# TopSheet.net
KiCad netlist of a schematic drawn in Altium Designer
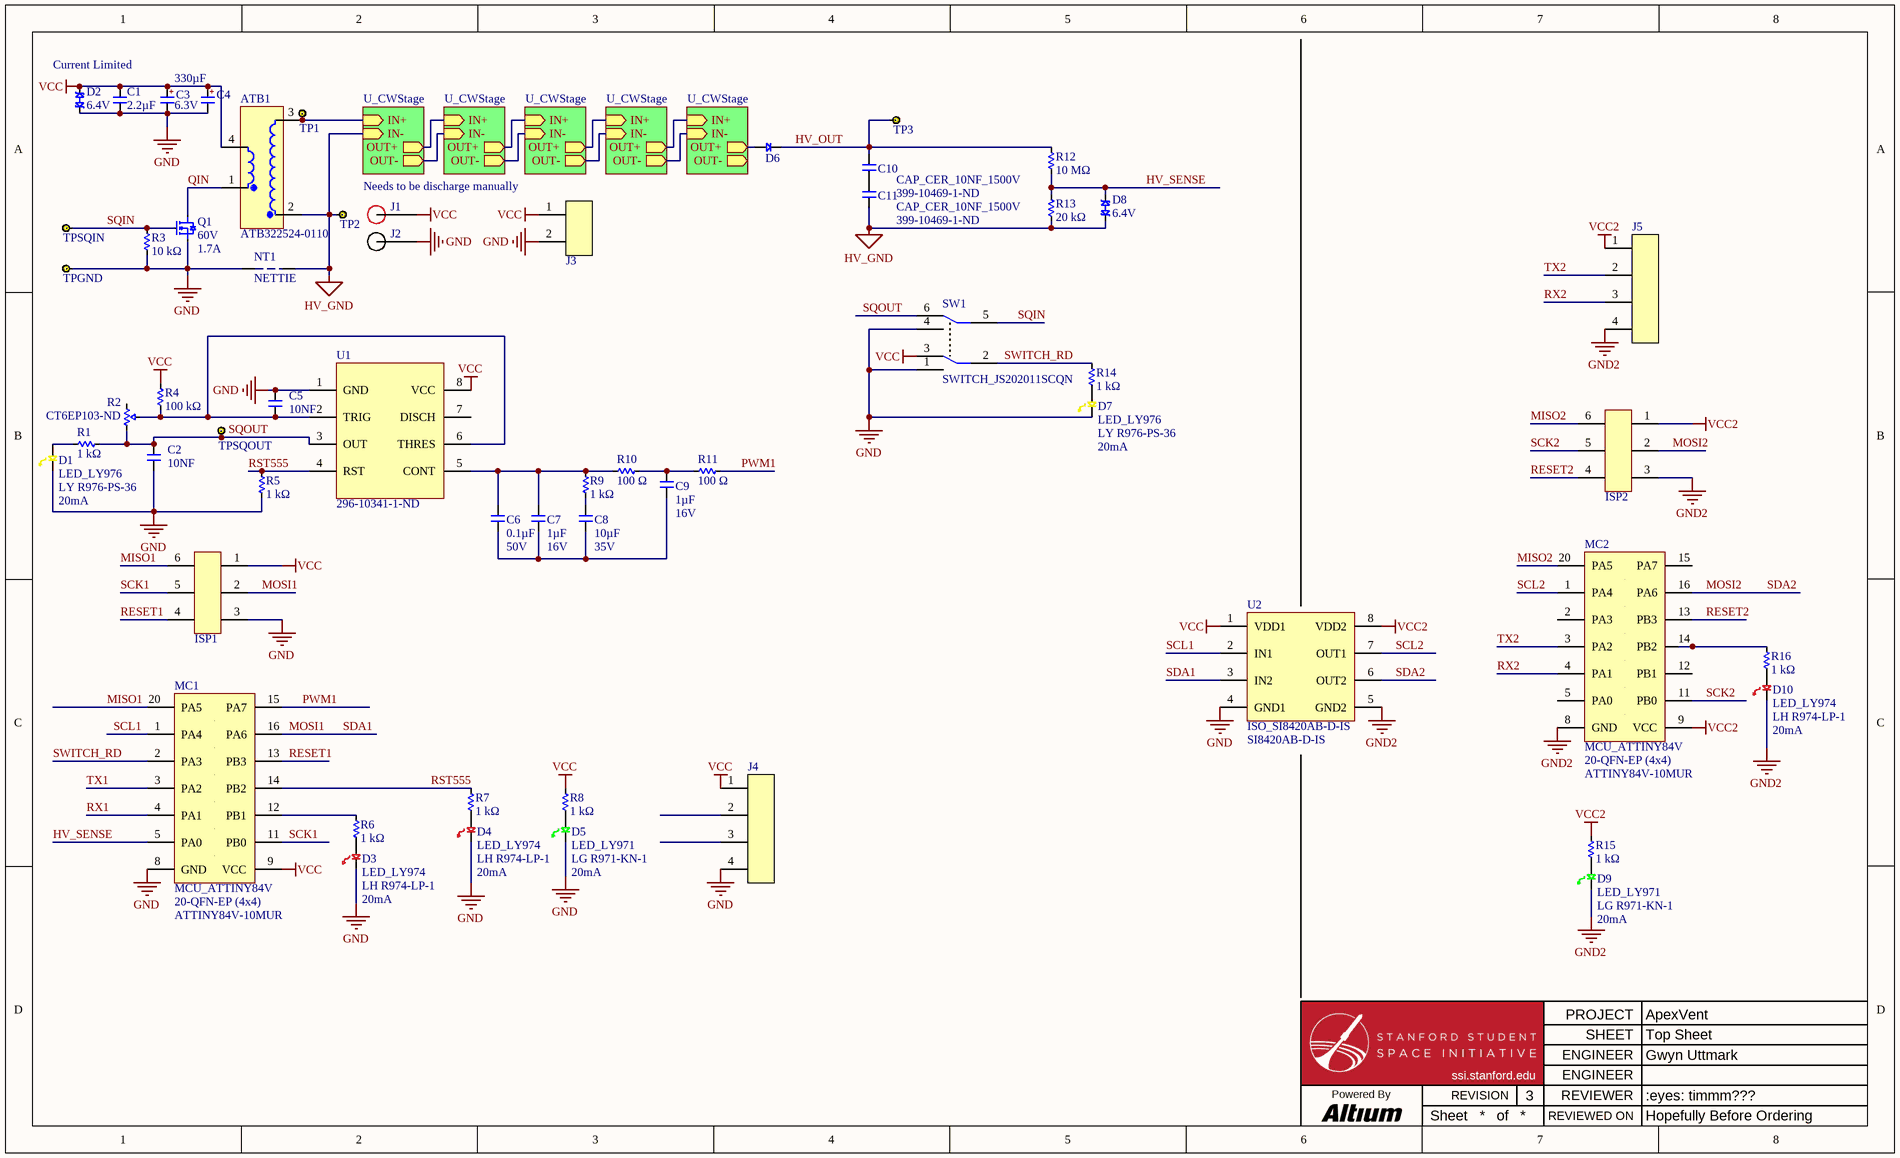
[diagram p0: TopSheet.SchDoc]

(export (version "E")
  (design (tool "Eeschema 10.0.6"))
  (components
    (comp (ref "ATB1")
      (value "ATB322524-0110")
      (footprint "ATB3225")
      (libsource (lib "Stanford Student Space Initiative") (part "IND_ATB322524"))
    )
    (comp (ref "C1")
      (value "__template_cap")
      (footprint "C0603")
      (description "CAP CER 2.2UF 16V X5R 0603 10%")
      (fields (field (name "CAPACITANCE (SHORTHAND)") "2.2µF"))
      (libsource (lib "passives") (part "__template_cap"))
    )
    (comp (ref "C2") (value "10NF") (footprint "C1206") (libsource (lib "SSI") (part "CAP_CER_10NF_1500V")))
    (comp (ref "C3")
      (value "CAP_TANT_330UF_6.3V")
      (footprint "C1210P")
      (description "330UF 1210 SMD TANTALUM CAPACITOR")
      (fields
        (field (name "MANUFACTURER") "AVX Corporation")
        (field (name "MANUFACTURER PART NUMBER") "F950J337KBAAQ2")
        (field (name "CAPACITANCE") "330µF")
        (field (name "VOLTAGE - RATED") "6.3V")
      )
      (libsource (lib "SSI") (part "CAP_TANT_330UF_6.3V"))
    )
    (comp (ref "C4")
      (value "CAP_TANT_330UF_6.3V")
      (footprint "C1210P")
      (description "330UF 1210 SMD TANTALUM CAPACITOR")
      (fields
        (field (name "MANUFACTURER") "AVX Corporation")
        (field (name "MANUFACTURER PART NUMBER") "F950J337KBAAQ2")
      )
      (libsource (lib "SSI") (part "CAP_TANT_330UF_6.3V"))
    )
    (comp (ref "C5") (value "10NF") (footprint "C1206") (libsource (lib "SSI") (part "CAP_CER_10NF_1500V")))
    (comp (ref "C6")
      (value "__template_cap")
      (footprint "C0603")
      (description "CAP CER 0603 0.1µF X7R 50V 10%")
      (fields
        (field (name "CAPACITANCE (SHORTHAND)") "0.1µF")
        (field (name "RATED VOLTAGE") "50V")
        (field (name "MANUFACTURER") "Murata Electronics North America")
      )
      (libsource (lib "passives") (part "__template_cap"))
    )
    (comp (ref "C7")
      (value "__template_cap")
      (footprint "C0603")
      (description "CAP CER 0603 1µF X7R 16V 10%")
      (fields
        (field (name "CAPACITANCE (SHORTHAND)") "1µF")
        (field (name "RATED VOLTAGE") "16V")
        (field (name "MANUFACTURER") "Murata Electronics North America")
      )
      (libsource (lib "passives") (part "__template_cap"))
    )
    (comp (ref "C8")
      (value "__template_cap")
      (footprint "C0603")
      (description "CAP CER 10UF 35V X5R 0603 20%")
      (fields
        (field (name "CAPACITANCE (SHORTHAND)") "10µF")
        (field (name "RATED VOLTAGE") "35V")
        (field (name "MANUFACTURER") "Murata Electronics North America")
      )
      (libsource (lib "passives") (part "__template_cap"))
    )
    (comp (ref "C9")
      (value "__template_cap")
      (footprint "C0603")
      (description "CAP CER 0603 1µF X7R 16V 10%")
      (fields
        (field (name "CAPACITANCE (SHORTHAND)") "1µF")
        (field (name "RATED VOLTAGE") "16V")
        (field (name "MANUFACTURER") "Murata Electronics North America")
      )
      (libsource (lib "passives") (part "__template_cap"))
    )
    (comp (ref "C10")
      (value "CAP_CER_10NF_1500V")
      (footprint "C1206")
      (fields (field (name "SUPPLIER PART NUMBER 1") "399-10469-1-ND"))
      (libsource (lib "SSI") (part "CAP_CER_10NF_1500V"))
    )
    (comp (ref "C11")
      (value "CAP_CER_10NF_1500V")
      (footprint "C1206")
      (fields (field (name "SUPPLIER PART NUMBER 1") "399-10469-1-ND"))
      (libsource (lib "SSI") (part "CAP_CER_10NF_1500V"))
    )
    (comp (ref "D1")
      (value "LED_LY976")
      (footprint "0805_Diode")
      (description "LED 0805 YELLOW 20MA")
      (fields
        (field (name "MANUFACTURER PART NUMBER") "LY R976-PS-36")
        (field (name "CURRENT - TEST") "20mA")
        (field (name "MANUFACTURER") "OSRAM Opto Semiconductors Inc")
      )
      (libsource (lib "Stanford Student Space Initiative") (part "LED_LY976"))
    )
    (comp (ref "D2")
      (value "TVS_BI_SMDJ5.0CA")
      (footprint "SMC")
      (description "DIODE TVS 5.0V 3000W 5% BI SMD")
      (fields
        (field (name "MANUFACTURER") "Littelfuse Inc")
        (field (name "MANUFACTURER PART NUMBER") "SMDJ5.0CA")
        (field (name "VOLTAGE - BREAKDOWN") "6.4V")
      )
      (libsource (lib "SSI") (part "TVS_BI_SMDJ5.0CA"))
    )
    (comp (ref "D3")
      (value "LED_LY974")
      (footprint "0805_Diode")
      (description "LED 0805 RED 20MA")
      (fields
        (field (name "MANUFACTURER PART NUMBER") "LH R974-LP-1")
        (field (name "CURRENT - TEST") "20mA")
        (field (name "MANUFACTURER") "OSRAM Opto Semiconductors Inc")
      )
      (libsource (lib "Stanford Student Space Initiative") (part "LED_LY974"))
    )
    (comp (ref "D4")
      (value "LED_LY974")
      (footprint "0805_Diode")
      (description "LED 0805 RED 20MA")
      (fields
        (field (name "MANUFACTURER PART NUMBER") "LH R974-LP-1")
        (field (name "CURRENT - TEST") "20mA")
        (field (name "MANUFACTURER") "OSRAM Opto Semiconductors Inc")
      )
      (libsource (lib "Stanford Student Space Initiative") (part "LED_LY974"))
    )
    (comp (ref "D5")
      (value "LED_LY971")
      (footprint "0805_Diode")
      (description "LED 0805 GREEN 20MA")
      (fields
        (field (name "MANUFACTURER PART NUMBER") "LG R971-KN-1")
        (field (name "CURRENT - TEST") "20mA")
        (field (name "MANUFACTURER") "OSRAM Opto Semiconductors Inc")
      )
      (libsource (lib "Stanford Student Space Initiative") (part "LED_LY971"))
    )
    (comp (ref "D6")
      (value "DIODE_ S1PM-M3/84A")
      (footprint "DO-220AA")
      (libsource (lib "SSI") (part "DIODE_ S1PM-M3/84A"))
    )
    (comp (ref "D7")
      (value "LED_LY976")
      (footprint "0805_Diode")
      (description "LED 0805 YELLOW 20MA")
      (fields
        (field (name "MANUFACTURER PART NUMBER") "LY R976-PS-36")
        (field (name "CURRENT - TEST") "20mA")
        (field (name "MANUFACTURER") "OSRAM Opto Semiconductors Inc")
      )
      (libsource (lib "Stanford Student Space Initiative") (part "LED_LY976"))
    )
    (comp (ref "D8")
      (value "TVS_BI_SMDJ5.0CA")
      (footprint "SMC")
      (description "DIODE TVS 5.0V 3000W 5% BI SMD")
      (fields
        (field (name "MANUFACTURER") "Littelfuse Inc")
        (field (name "MANUFACTURER PART NUMBER") "SMDJ5.0CA")
        (field (name "VOLTAGE - BREAKDOWN") "6.4V")
      )
      (libsource (lib "SSI") (part "TVS_BI_SMDJ5.0CA"))
    )
    (comp (ref "D9")
      (value "LED_LY971")
      (footprint "0805_Diode")
      (description "LED 0805 GREEN 20MA")
      (fields
        (field (name "MANUFACTURER PART NUMBER") "LG R971-KN-1")
        (field (name "CURRENT - TEST") "20mA")
        (field (name "MANUFACTURER") "OSRAM Opto Semiconductors Inc")
      )
      (libsource (lib "Stanford Student Space Initiative") (part "LED_LY971"))
    )
    (comp (ref "D10")
      (value "LED_LY974")
      (footprint "0805_Diode")
      (description "LED 0805 RED 20MA")
      (fields
        (field (name "MANUFACTURER PART NUMBER") "LH R974-LP-1")
        (field (name "CURRENT - TEST") "20mA")
        (field (name "MANUFACTURER") "OSRAM Opto Semiconductors Inc")
      )
      (libsource (lib "Stanford Student Space Initiative") (part "LED_LY974"))
    )
    (comp (ref "ISP1")
      (value "CONN_2x3_15-91-2060")
      (footprint "MOLEX_15-91-2060")
      (description "CONN HEADER 6POS .100\" VERT TIN")
      (fields
        (field (name "MANUFACTURER") "Molex Inc")
        (field (name "MANUFACTURER PART NUMBER") "0015912060")
      )
      (libsource (lib "Stanford Student Space Initiative") (part "CONN_2x3_15-91-2060"))
    )
    (comp (ref "ISP2")
      (value "CONN_2x3_15-91-2060")
      (footprint "MOLEX_15-91-2060")
      (description "CONN HEADER 6POS .100\" VERT TIN")
      (fields
        (field (name "MANUFACTURER") "Molex Inc")
        (field (name "MANUFACTURER PART NUMBER") "0015912060")
      )
      (libsource (lib "Stanford Student Space Initiative") (part "CONN_2x3_15-91-2060"))
    )
    (comp (ref "J1")
      (value "J2")
      (footprint "CONN_BANANA_CALTEST_RED")
      (fields
        (field (name "MANUFACTURER") "B&K Precision")
        (field (name "MANUFACTURER PART NUMBER") "CT3151-2")
      )
      (libsource (lib "SSI") (part "CONN_BANNANAJACK_RA_RED_CT3151SP"))
    )
    (comp (ref "J2")
      (value "CONN_BANNANAJACK_RA_BLACK_CT3151SP")
      (footprint "CONN_BANANA_CALTEST_BLACk")
      (fields
        (field (name "MANUFACTURER") "B&K Precision")
        (field (name "MANUFACTURER PART NUMBER") "CT3151-0")
      )
      (libsource (lib "SSI") (part "CONN_BANNANAJACK_RA_BLACK_CT3151SP"))
    )
    (comp (ref "J3")
      (value "CONN HEADER 2POS VERT T/H")
      (footprint "CONN_1x2_100MIL")
      (fields (field (name "MANUFACTURER") "FCI") (field (name "MANUFACTURER PART NUMBER") "77311-118-02LF"))
      (libsource (lib "SSI") (part "CONN_1x2"))
    )
    (comp (ref "J4")
      (value "CONN_1x4")
      (footprint "CONN_1x4_100MIL")
      (description "CONN HEADER 4POS T/H")
      (libsource (lib "Stanford Student Space Initiative") (part "Symbol"))
    )
    (comp (ref "J5")
      (value "CONN_1x4")
      (footprint "CONN_1x4_100MIL")
      (description "CONN HEADER 4POS T/H")
      (libsource (lib "Stanford Student Space Initiative") (part "Symbol"))
    )
    (comp (ref "MC1")
      (value "MCU_ATTINY84V")
      (footprint "20QFN4")
      (description "Attiny84 Surface Mount Extended Voltage Range")
      (fields
        (field (name "SUPPLIER DEVICE PACKAGE") "20-QFN-EP (4x4)")
        (field (name "MANUFACTURER PART NUMBER") "ATTINY84V-10MUR")
        (field (name "MANUFACTURER") "Microchip Technology")
      )
      (libsource (lib "Stanford Student Space Initiative") (part "MCU_ATTINY84V"))
    )
    (comp (ref "MC2")
      (value "MCU_ATTINY84V")
      (footprint "20QFN4")
      (description "Attiny84 Surface Mount Extended Voltage Range")
      (fields
        (field (name "SUPPLIER DEVICE PACKAGE") "20-QFN-EP (4x4)")
        (field (name "MANUFACTURER PART NUMBER") "ATTINY84V-10MUR")
        (field (name "MANUFACTURER") "Microchip Technology")
      )
      (libsource (lib "Stanford Student Space Initiative") (part "MCU_ATTINY84V"))
    )
    (comp (ref "NT1")
      (value "NETTIE")
      (footprint "NETTIE_10MIL")
      (description "Net tie. Use sparingly.")
      (libsource (lib "Stanford Student Space Initiative") (part "NETTIE"))
    )
    (comp (ref "Q1")
      (value "MOSFET N-CH 60V 1.7A SSOT3")
      (footprint "3SOT23")
      (fields
        (field (name "MANUFACTURER") "Fairchild Semiconductor")
        (field (name "MANUFACTURER PART NUMBER") "FDN5630")
        (field (name "DRAIN TO SOURCE VOLTAGE (VDSS)") "60V")
        (field (name "CURRENT - CONTINUOUS DRAIN (ID) @ 25° C") "1.7A")
      )
      (libsource (lib "transistor_fet") (part "NFET_FDN5630"))
    )
    (comp (ref "R1")
      (value "__template_resistor")
      (footprint "R0805")
      (description "RES SMD 1K OHM 1% 1/8W 0805")
      (fields
        (field (name "RESISTANCE") "1 kΩ")
        (field (name "MANUFACTURER PART NUMBER") "RC0805FR-071KL")
        (field (name "MANUFACTURER") "Yageo")
      )
      (libsource (lib "passives") (part "__template_resistor"))
    )
    (comp (ref "R2")
      (value "POT_10K_CT6EP103")
      (footprint "CT6EP")
      (fields
        (field (name "MANUFACTURER") "Copal Electronics Inc")
        (field (name "MANUFACTURER PART NUMBER") "CT6EP103")
        (field (name "TOLERANCE") "±10%")
        (field (name "SUPPLIER PART NUMBER 1") "CT6EP103-ND")
      )
      (libsource (lib "SSI") (part "POT_10K_CT6EP103"))
    )
    (comp (ref "R3")
      (value "__template_resistor")
      (footprint "R0603")
      (description "RES SMD 10K OHM 1% 1/10W 0603")
      (fields
        (field (name "RESISTANCE") "10 kΩ")
        (field (name "MANUFACTURER PART NUMBER") "RC0603FR-0710KL")
        (field (name "MANUFACTURER") "Yageo")
      )
      (libsource (lib "passives") (part "__template_resistor"))
    )
    (comp (ref "R4")
      (value "__template_resistor")
      (footprint "R0805")
      (description "RES SMD 100K OHM 1% 1/8W 0805")
      (fields (field (name "RESISTANCE") "100 kΩ"))
      (libsource (lib "passives") (part "__template_resistor"))
    )
    (comp (ref "R5")
      (value "__template_resistor")
      (footprint "R0805")
      (description "RES SMD 1K OHM 1% 1/8W 0805")
      (fields
        (field (name "RESISTANCE") "1 kΩ")
        (field (name "MANUFACTURER PART NUMBER") "RC0805FR-071KL")
        (field (name "MANUFACTURER") "Yageo")
      )
      (libsource (lib "passives") (part "__template_resistor"))
    )
    (comp (ref "R6")
      (value "__template_resistor")
      (footprint "R0805")
      (description "RES SMD 1K OHM 1% 1/8W 0805")
      (fields
        (field (name "RESISTANCE") "1 kΩ")
        (field (name "MANUFACTURER PART NUMBER") "RC0805FR-071KL")
        (field (name "MANUFACTURER") "Yageo")
      )
      (libsource (lib "passives") (part "__template_resistor"))
    )
    (comp (ref "R7")
      (value "__template_resistor")
      (footprint "R0805")
      (description "RES SMD 1K OHM 1% 1/8W 0805")
      (fields
        (field (name "RESISTANCE") "1 kΩ")
        (field (name "MANUFACTURER PART NUMBER") "RC0805FR-071KL")
        (field (name "MANUFACTURER") "Yageo")
      )
      (libsource (lib "passives") (part "__template_resistor"))
    )
    (comp (ref "R8")
      (value "__template_resistor")
      (footprint "R0805")
      (description "RES SMD 1K OHM 1% 1/8W 0805")
      (fields
        (field (name "RESISTANCE") "1 kΩ")
        (field (name "MANUFACTURER PART NUMBER") "RC0805FR-071KL")
        (field (name "MANUFACTURER") "Yageo")
      )
      (libsource (lib "passives") (part "__template_resistor"))
    )
    (comp (ref "R9")
      (value "__template_resistor")
      (footprint "R0805")
      (description "RES SMD 1K OHM 1% 1/8W 0805")
      (fields
        (field (name "RESISTANCE") "1 kΩ")
        (field (name "MANUFACTURER PART NUMBER") "RC0805FR-071KL")
        (field (name "MANUFACTURER") "Yageo")
      )
      (libsource (lib "passives") (part "__template_resistor"))
    )
    (comp (ref "R10")
      (value "__template_resistor")
      (footprint "R0805")
      (description "RES SMD 100 OHM 1% 1/8W 0805")
      (fields
        (field (name "RESISTANCE") "100 Ω")
        (field (name "MANUFACTURER PART NUMBER") "RC0805FR-07100RL")
        (field (name "MANUFACTURER") "Yageo")
      )
      (libsource (lib "passives") (part "__template_resistor"))
    )
    (comp (ref "R11")
      (value "__template_resistor")
      (footprint "R0805")
      (description "RES SMD 100 OHM 1% 1/8W 0805")
      (fields
        (field (name "RESISTANCE") "100 Ω")
        (field (name "MANUFACTURER PART NUMBER") "RC0805FR-07100RL")
        (field (name "MANUFACTURER") "Yageo")
      )
      (libsource (lib "passives") (part "__template_resistor"))
    )
    (comp (ref "R12")
      (value "__template_resistor")
      (footprint "R0805")
      (description "RES SMD 10M OHM 1% 1/8W 0805")
      (fields
        (field (name "RESISTANCE") "10 MΩ")
        (field (name "MANUFACTURER PART NUMBER") "RC0805FR-0710ML")
        (field (name "MANUFACTURER") "Yageo")
      )
      (libsource (lib "passives") (part "__template_resistor"))
    )
    (comp (ref "R13")
      (value "__template_resistor")
      (footprint "R0805")
      (description "RES SMD 20K OHM 1% 1/8W 0805")
      (fields
        (field (name "RESISTANCE") "20 kΩ")
        (field (name "MANUFACTURER PART NUMBER") "RC0805FR-0720KL")
        (field (name "MANUFACTURER") "Yageo")
      )
      (libsource (lib "passives") (part "__template_resistor"))
    )
    (comp (ref "R14")
      (value "__template_resistor")
      (footprint "R0805")
      (description "RES SMD 1K OHM 1% 1/8W 0805")
      (fields
        (field (name "RESISTANCE") "1 kΩ")
        (field (name "MANUFACTURER PART NUMBER") "RC0805FR-071KL")
        (field (name "MANUFACTURER") "Yageo")
      )
      (libsource (lib "passives") (part "__template_resistor"))
    )
    (comp (ref "R15")
      (value "__template_resistor")
      (footprint "R0805")
      (description "RES SMD 1K OHM 1% 1/8W 0805")
      (fields
        (field (name "RESISTANCE") "1 kΩ")
        (field (name "MANUFACTURER PART NUMBER") "RC0805FR-071KL")
        (field (name "MANUFACTURER") "Yageo")
      )
      (libsource (lib "passives") (part "__template_resistor"))
    )
    (comp (ref "R16")
      (value "__template_resistor")
      (footprint "R0805")
      (description "RES SMD 1K OHM 1% 1/8W 0805")
      (fields
        (field (name "RESISTANCE") "1 kΩ")
        (field (name "MANUFACTURER PART NUMBER") "RC0805FR-071KL")
        (field (name "MANUFACTURER") "Yageo")
      )
      (libsource (lib "passives") (part "__template_resistor"))
    )
    (comp (ref "SW1")
      (value "SWITCH_JS202011SCQN")
      (footprint "SWITCH_DUAL_POS")
      (description "SWITCH SLIDE DPDT 0.3A 6V SMT")
      (fields
        (field (name "MANUFACTURER PART NUMBER") "JS202011SCQN")
        (field (name "MANUFACTURER") "C&K Components")
      )
      (libsource (lib "Stanford Student Space Initiative") (part "SWITCH_JS202011SCQN"))
    )
    (comp (ref "TP1")
      (value "TEST_POINT_BLACK_KEYSTONE_5001")
      (footprint "TEST_POINT_KEYSTONE_5001")
      (description "BLACK T/H TEST POINT")
      (fields
        (field (name "MANUFACTURER") "Keystone Electronics")
        (field (name "MANUFACTURER PART NUMBER") "5001")
      )
      (libsource (lib "SSI") (part "TEST_POINT_BLACK_KEYSTONE_5001"))
    )
    (comp (ref "TP2")
      (value "TEST_POINT_BLACK_KEYSTONE_5001")
      (footprint "TEST_POINT_KEYSTONE_5001")
      (description "BLACK T/H TEST POINT")
      (fields
        (field (name "MANUFACTURER") "Keystone Electronics")
        (field (name "MANUFACTURER PART NUMBER") "5001")
      )
      (libsource (lib "SSI") (part "TEST_POINT_BLACK_KEYSTONE_5001"))
    )
    (comp (ref "TP3")
      (value "TEST_POINT_BLACK_KEYSTONE_5001")
      (footprint "TEST_POINT_KEYSTONE_5001")
      (description "BLACK T/H TEST POINT")
      (fields
        (field (name "MANUFACTURER") "Keystone Electronics")
        (field (name "MANUFACTURER PART NUMBER") "5001")
      )
      (libsource (lib "SSI") (part "TEST_POINT_BLACK_KEYSTONE_5001"))
    )
    (comp (ref "TPGND")
      (value "TEST_POINT_BLACK_KEYSTONE_5001")
      (footprint "TEST_POINT_KEYSTONE_5001")
      (description "BLACK T/H TEST POINT")
      (fields
        (field (name "MANUFACTURER") "Keystone Electronics")
        (field (name "MANUFACTURER PART NUMBER") "5001")
      )
      (libsource (lib "SSI") (part "TEST_POINT_BLACK_KEYSTONE_5001"))
    )
    (comp (ref "TPSQIN")
      (value "TEST_POINT_BLACK_KEYSTONE_5001")
      (footprint "TEST_POINT_KEYSTONE_5001")
      (description "BLACK T/H TEST POINT")
      (fields
        (field (name "MANUFACTURER") "Keystone Electronics")
        (field (name "MANUFACTURER PART NUMBER") "5001")
      )
      (libsource (lib "SSI") (part "TEST_POINT_BLACK_KEYSTONE_5001"))
    )
    (comp (ref "TPSQOUT")
      (value "TEST_POINT_BLACK_KEYSTONE_5001")
      (footprint "TEST_POINT_KEYSTONE_5001")
      (description "BLACK T/H TEST POINT")
      (fields
        (field (name "MANUFACTURER") "Keystone Electronics")
        (field (name "MANUFACTURER PART NUMBER") "5001")
      )
      (libsource (lib "SSI") (part "TEST_POINT_BLACK_KEYSTONE_5001"))
    )
    (comp (ref "U1")
      (value "TIM_TLC555")
      (footprint "8SOIC150")
      (description "IC OSC SGL TIMER 2.1MHZ")
      (fields
        (field (name "MANUFACTURER") "Texas Instruments")
        (field (name "MANUFACTURER PART NUMBER") "TLC555QDR")
        (field (name "SUPPLIER PART NUMBER 1") "296-10341-1-ND")
      )
      (libsource (lib "SSI") (part "TIM_TLC555"))
    )
    (comp (ref "U2")
      (value "ISO_SI8420AB-D-IS")
      (footprint "8SOIC150")
      (description "IC ISOLATOR 2CH 5.5V 8-SOIC")
      (fields
        (field (name "MANUFACTURER PART NUMBER") "SI8420AB-D-IS")
        (field (name "MANUFACTURER") "Silicon Laboratories  Inc")
      )
      (libsource (lib "Stanford Student Space Initiative") (part "ISO_SI8420AB-D-IS"))
    )
  )
  (nets
    (net (code "1") (name "/HV_OUT") (class "Default")
      (node (ref "C10") (pin "2") (pintype "passive"))
      (node (ref "D6") (pin "1") (pintype "passive"))
      (node (ref "R12") (pin "1") (pintype "passive"))
      (node (ref "TP3") (pin "1") (pinfunction "1_1") (pintype "passive"))
    )
    (net (code "2") (name "/HV_SENSE") (class "Default")
      (node (ref "D8") (pin "2") (pintype "passive"))
      (node (ref "MC1") (pin "5") (pinfunction "PA0_5") (pintype "power_in"))
      (node (ref "R12") (pin "2") (pintype "passive"))
      (node (ref "R13") (pin "1") (pintype "passive"))
    )
    (net (code "3") (name "/IN+") (class "Default")
      (node (ref "ATB1") (pin "3") (pinfunction "3_3") (pintype "power_in"))
      (node (ref "TP1") (pin "1") (pinfunction "1_1") (pintype "passive"))
    )
    (net (code "4") (name "/MISO1") (class "Default")
      (node (ref "ISP1") (pin "6") (pintype "passive"))
      (node (ref "MC1") (pin "20") (pinfunction "PA5_20") (pintype "power_in"))
    )
    (net (code "5") (name "/MISO2") (class "Default")
      (node (ref "ISP2") (pin "6") (pintype "passive"))
      (node (ref "MC2") (pin "20") (pinfunction "PA5_20") (pintype "power_in"))
    )
    (net (code "6") (name "/MOSI1") (class "Default")
      (node (ref "ISP1") (pin "2") (pintype "passive"))
      (node (ref "MC1") (pin "16") (pinfunction "PA6_16") (pintype "power_in"))
      (node (ref "U2") (pin "3") (pinfunction "IN2_3") (pintype "passive"))
    )
    (net (code "7") (name "/MOSI2") (class "Default")
      (node (ref "ISP2") (pin "2") (pintype "passive"))
      (node (ref "MC2") (pin "16") (pinfunction "PA6_16") (pintype "power_in"))
      (node (ref "U2") (pin "6") (pinfunction "OUT2_6") (pintype "passive"))
    )
    (net (code "8") (name "/OUT+") (class "Default") (node (ref "D6") (pin "2") (pintype "passive")))
    (net (code "18") (name "/PWM1") (class "Default")
      (node (ref "MC1") (pin "15") (pinfunction "PA7_15") (pintype "power_in"))
      (node (ref "R11") (pin "2") (pintype "passive"))
    )
    (net (code "19") (name "/QIN") (class "Default")
      (node (ref "ATB1") (pin "1") (pinfunction "4_1") (pintype "power_in"))
      (node (ref "Q1") (pin "3") (pintype "passive"))
    )
    (net (code "20") (name "/RESET1") (class "Default")
      (node (ref "ISP1") (pin "4") (pintype "passive"))
      (node (ref "MC1") (pin "13") (pinfunction "PB3_13") (pintype "power_in"))
    )
    (net (code "21") (name "/RESET2") (class "Default")
      (node (ref "ISP2") (pin "4") (pintype "passive"))
      (node (ref "MC2") (pin "13") (pinfunction "PB3_13") (pintype "power_in"))
    )
    (net (code "22") (name "/RST555") (class "Default")
      (node (ref "MC1") (pin "14") (pinfunction "PB2_14") (pintype "power_in"))
      (node (ref "R5") (pin "2") (pintype "passive"))
      (node (ref "R7") (pin "2") (pintype "passive"))
      (node (ref "U1") (pin "4") (pinfunction "RST_4") (pintype "passive"))
    )
    (net (code "23") (name "/RX1") (class "Default")
      (node (ref "MC1") (pin "4") (pinfunction "PA1_4") (pintype "power_in"))
    )
    (net (code "24") (name "/RX2") (class "Default")
      (node (ref "J5") (pin "3") (pinfunction "3_3") (pintype "passive"))
      (node (ref "MC2") (pin "4") (pinfunction "PA1_4") (pintype "power_in"))
    )
    (net (code "25") (name "/SCK1") (class "Default")
      (node (ref "ISP1") (pin "5") (pintype "passive"))
      (node (ref "MC1") (pin "11") (pinfunction "PB0_11") (pintype "power_in"))
    )
    (net (code "26") (name "/SCK2") (class "Default")
      (node (ref "ISP2") (pin "5") (pintype "passive"))
      (node (ref "MC2") (pin "11") (pinfunction "PB0_11") (pintype "power_in"))
    )
    (net (code "27") (name "/SCL1") (class "Default")
      (node (ref "MC1") (pin "1") (pinfunction "PA4_1") (pintype "power_in"))
      (node (ref "U2") (pin "2") (pinfunction "IN1_2") (pintype "passive"))
    )
    (net (code "28") (name "/SCL2") (class "Default")
      (node (ref "MC2") (pin "1") (pinfunction "PA4_1") (pintype "power_in"))
      (node (ref "U2") (pin "7") (pinfunction "OUT1_7") (pintype "passive"))
    )
    (net (code "29") (name "/SQIN") (class "Default")
      (node (ref "Q1") (pin "1") (pintype "passive"))
      (node (ref "R3") (pin "2") (pintype "passive"))
      (node (ref "SW1") (pin "5") (pinfunction "5_5") (pintype "passive"))
      (node (ref "TPSQIN") (pin "1") (pinfunction "1_1") (pintype "passive"))
    )
    (net (code "30") (name "/SQOUT") (class "Default")
      (node (ref "C2") (pin "1") (pintype "passive"))
      (node (ref "R1") (pin "1") (pintype "passive"))
      (node (ref "R2") (pin "1") (pinfunction "1_1") (pintype "passive"))
      (node (ref "SW1") (pin "6") (pinfunction "6_6") (pintype "passive"))
      (node (ref "TPSQOUT") (pin "1") (pinfunction "1_1") (pintype "passive"))
      (node (ref "U1") (pin "3") (pinfunction "OUT_3") (pintype "passive"))
    )
    (net (code "31") (name "/SWITCH_RD") (class "Default")
      (node (ref "MC1") (pin "2") (pinfunction "PA3_2") (pintype "power_in"))
      (node (ref "R14") (pin "2") (pintype "passive"))
      (node (ref "SW1") (pin "2") (pinfunction "2_2") (pintype "passive"))
    )
    (net (code "32") (name "/TX1") (class "Default")
      (node (ref "MC1") (pin "3") (pinfunction "PA2_3") (pintype "power_in"))
    )
    (net (code "33") (name "/TX2") (class "Default")
      (node (ref "J5") (pin "2") (pinfunction "2_2") (pintype "passive"))
      (node (ref "MC2") (pin "3") (pinfunction "PA2_3") (pintype "power_in"))
    )
    (net (code "34") (name "GND") (class "Default")
      (node (ref "C1") (pin "2") (pintype "passive"))
      (node (ref "C2") (pin "2") (pintype "passive"))
      (node (ref "C3") (pin "2") (pintype "passive"))
      (node (ref "C4") (pin "2") (pintype "passive"))
      (node (ref "C5") (pin "1") (pintype "passive"))
      (node (ref "D1") (pin "1") (pintype "passive"))
      (node (ref "D2") (pin "1") (pintype "passive"))
      (node (ref "D3") (pin "1") (pintype "passive"))
      (node (ref "D4") (pin "1") (pintype "passive"))
      (node (ref "D5") (pin "1") (pintype "passive"))
      (node (ref "D7") (pin "1") (pintype "passive"))
      (node (ref "ISP1") (pin "3") (pintype "passive"))
      (node (ref "J2") (pin "SIG") (pinfunction "SIG_SIG") (pintype "passive"))
      (node (ref "J3") (pin "2") (pinfunction "2_2") (pintype "passive"))
      (node (ref "J4") (pin "4") (pinfunction "4_4") (pintype "passive"))
      (node (ref "MC1") (pin "8") (pinfunction "GND_8") (pintype "power_in"))
      (node (ref "NT1") (pin "1") (pinfunction "1_1") (pintype "passive"))
      (node (ref "Q1") (pin "2") (pintype "passive"))
      (node (ref "R3") (pin "1") (pintype "passive"))
      (node (ref "R5") (pin "1") (pintype "passive"))
      (node (ref "SW1") (pin "1") (pinfunction "1_1") (pintype "passive"))
      (node (ref "SW1") (pin "4") (pinfunction "4_4") (pintype "passive"))
      (node (ref "TPGND") (pin "1") (pinfunction "1_1") (pintype "passive"))
      (node (ref "U1") (pin "1") (pinfunction "GND_1") (pintype "passive"))
      (node (ref "U2") (pin "4") (pinfunction "GND1_4") (pintype "passive"))
    )
    (net (code "35") (name "GND2") (class "Default")
      (node (ref "D10") (pin "1") (pintype "passive"))
      (node (ref "D9") (pin "1") (pintype "passive"))
      (node (ref "ISP2") (pin "3") (pintype "passive"))
      (node (ref "J5") (pin "4") (pinfunction "4_4") (pintype "passive"))
      (node (ref "MC2") (pin "8") (pinfunction "GND_8") (pintype "power_in"))
      (node (ref "U2") (pin "5") (pinfunction "GND2_5") (pintype "passive"))
    )
    (net (code "36") (name "HV_GND") (class "Default")
      (node (ref "ATB1") (pin "2") (pinfunction "2_2") (pintype "power_in"))
      (node (ref "C11") (pin "1") (pintype "passive"))
      (node (ref "D8") (pin "1") (pintype "passive"))
      (node (ref "NT1") (pin "2") (pinfunction "2_2") (pintype "passive"))
      (node (ref "R13") (pin "2") (pintype "passive"))
      (node (ref "TP2") (pin "1") (pinfunction "1_1") (pintype "passive"))
    )
    (net (code "37") (name "Net-(C6-Pad2)") (class "Default")
      (node (ref "C6") (pin "2") (pintype "passive"))
      (node (ref "C7") (pin "2") (pintype "passive"))
      (node (ref "C8") (pin "2") (pintype "passive"))
      (node (ref "C9") (pin "2") (pintype "passive"))
    )
    (net (code "38") (name "Net-(C8-Pad1)") (class "Default")
      (node (ref "C8") (pin "1") (pintype "passive"))
      (node (ref "R9") (pin "1") (pintype "passive"))
    )
    (net (code "39") (name "Net-(C9-Pad1)") (class "Default")
      (node (ref "C9") (pin "1") (pintype "passive"))
      (node (ref "R10") (pin "2") (pintype "passive"))
      (node (ref "R11") (pin "1") (pintype "passive"))
    )
    (net (code "40") (name "Net-(C10-Pad1)") (class "Default")
      (node (ref "C10") (pin "1") (pintype "passive"))
      (node (ref "C11") (pin "2") (pintype "passive"))
    )
    (net (code "41") (name "Net-(D1-Pad2)") (class "Default")
      (node (ref "D1") (pin "2") (pintype "passive"))
      (node (ref "R1") (pin "2") (pintype "passive"))
    )
    (net (code "42") (name "Net-(D3-Pad2)") (class "Default")
      (node (ref "D3") (pin "2") (pintype "passive"))
      (node (ref "R6") (pin "1") (pintype "passive"))
    )
    (net (code "43") (name "Net-(D4-Pad2)") (class "Default")
      (node (ref "D4") (pin "2") (pintype "passive"))
      (node (ref "R7") (pin "1") (pintype "passive"))
    )
    (net (code "44") (name "Net-(D5-Pad2)") (class "Default")
      (node (ref "D5") (pin "2") (pintype "passive"))
      (node (ref "R8") (pin "1") (pintype "passive"))
    )
    (net (code "45") (name "Net-(D7-Pad2)") (class "Default")
      (node (ref "D7") (pin "2") (pintype "passive"))
      (node (ref "R14") (pin "1") (pintype "passive"))
    )
    (net (code "46") (name "Net-(D9-Pad2)") (class "Default")
      (node (ref "D9") (pin "2") (pintype "passive"))
      (node (ref "R15") (pin "1") (pintype "passive"))
    )
    (net (code "47") (name "Net-(D10-Pad2)") (class "Default")
      (node (ref "D10") (pin "2") (pintype "passive"))
      (node (ref "R16") (pin "1") (pintype "passive"))
    )
    (net (code "48") (name "Net-(MC1-PB1)") (class "Default")
      (node (ref "MC1") (pin "12") (pinfunction "PB1_12") (pintype "power_in"))
      (node (ref "R6") (pin "2") (pintype "passive"))
    )
    (net (code "49") (name "Net-(MC2-PB2)") (class "Default")
      (node (ref "MC2") (pin "14") (pinfunction "PB2_14") (pintype "power_in"))
      (node (ref "R16") (pin "2") (pintype "passive"))
    )
    (net (code "50") (name "Net-(U1-CONT)") (class "Default")
      (node (ref "C6") (pin "1") (pintype "passive"))
      (node (ref "C7") (pin "1") (pintype "passive"))
      (node (ref "R10") (pin "1") (pintype "passive"))
      (node (ref "R9") (pin "2") (pintype "passive"))
      (node (ref "U1") (pin "5") (pinfunction "CONT_5") (pintype "passive"))
    )
    (net (code "51") (name "Net-(U1-THRES)") (class "Default")
      (node (ref "C5") (pin "2") (pintype "passive"))
      (node (ref "R2") (pin "2") (pinfunction "2_2") (pintype "passive"))
      (node (ref "R4") (pin "1") (pintype "passive"))
      (node (ref "U1") (pin "2") (pinfunction "TRIG_2") (pintype "passive"))
      (node (ref "U1") (pin "6") (pinfunction "THRES_6") (pintype "passive"))
    )
    (net (code "52") (name "VCC") (class "Default")
      (node (ref "ATB1") (pin "4") (pinfunction "4_4") (pintype "power_in"))
      (node (ref "C1") (pin "1") (pintype "passive"))
      (node (ref "C3") (pin "1") (pintype "passive"))
      (node (ref "C4") (pin "1") (pintype "passive"))
      (node (ref "D2") (pin "2") (pintype "passive"))
      (node (ref "ISP1") (pin "1") (pintype "passive"))
      (node (ref "J1") (pin "SIG") (pinfunction "SIG_SIG") (pintype "passive"))
      (node (ref "J3") (pin "1") (pinfunction "1_1") (pintype "passive"))
      (node (ref "J4") (pin "1") (pinfunction "1_1") (pintype "passive"))
      (node (ref "MC1") (pin "9") (pinfunction "VCC_9") (pintype "power_in"))
      (node (ref "R4") (pin "2") (pintype "passive"))
      (node (ref "R8") (pin "2") (pintype "passive"))
      (node (ref "SW1") (pin "3") (pinfunction "3_3") (pintype "passive"))
      (node (ref "U1") (pin "8") (pinfunction "VCC_8") (pintype "passive"))
      (node (ref "U2") (pin "1") (pinfunction "VDD1_1") (pintype "passive"))
    )
    (net (code "53") (name "VCC2") (class "Default")
      (node (ref "ISP2") (pin "1") (pintype "passive"))
      (node (ref "J5") (pin "1") (pinfunction "1_1") (pintype "passive"))
      (node (ref "MC2") (pin "9") (pinfunction "VCC_9") (pintype "power_in"))
      (node (ref "R15") (pin "2") (pintype "passive"))
      (node (ref "U2") (pin "8") (pinfunction "VDD2_8") (pintype "passive"))
    )
    (net (code "54") (name "unconnected-(J4-Pad2)") (class "Default")
      (node (ref "J4") (pin "2") (pinfunction "2_2") (pintype "passive"))
    )
    (net (code "55") (name "unconnected-(J4-Pad3)") (class "Default")
      (node (ref "J4") (pin "3") (pinfunction "3_3") (pintype "passive"))
    )
    (net (code "56") (name "unconnected-(MC1-DNC-Pad6)") (class "Default")
      (node (ref "MC1") (pin "6") (pinfunction "DNC_6") (pintype "passive"))
    )
    (net (code "57") (name "unconnected-(MC1-DNC-Pad7)") (class "Default")
      (node (ref "MC1") (pin "7") (pinfunction "DNC_7") (pintype "passive"))
    )
    (net (code "58") (name "unconnected-(MC1-DNC-Pad10)") (class "Default")
      (node (ref "MC1") (pin "10") (pinfunction "DNC_10") (pintype "passive"))
    )
    (net (code "59") (name "unconnected-(MC1-DNC-Pad17)") (class "Default")
      (node (ref "MC1") (pin "17") (pinfunction "DNC_17") (pintype "passive"))
    )
    (net (code "60") (name "unconnected-(MC1-DNC-Pad18)") (class "Default")
      (node (ref "MC1") (pin "18") (pinfunction "DNC_18") (pintype "passive"))
    )
    (net (code "61") (name "unconnected-(MC1-DNC-Pad19)") (class "Default")
      (node (ref "MC1") (pin "19") (pinfunction "DNC_19") (pintype "passive"))
    )
    (net (code "62") (name "unconnected-(MC2-DNC-Pad6)") (class "Default")
      (node (ref "MC2") (pin "6") (pinfunction "DNC_6") (pintype "passive"))
    )
    (net (code "63") (name "unconnected-(MC2-DNC-Pad7)") (class "Default")
      (node (ref "MC2") (pin "7") (pinfunction "DNC_7") (pintype "passive"))
    )
    (net (code "64") (name "unconnected-(MC2-DNC-Pad10)") (class "Default")
      (node (ref "MC2") (pin "10") (pinfunction "DNC_10") (pintype "passive"))
    )
    (net (code "65") (name "unconnected-(MC2-DNC-Pad17)") (class "Default")
      (node (ref "MC2") (pin "17") (pinfunction "DNC_17") (pintype "passive"))
    )
    (net (code "66") (name "unconnected-(MC2-DNC-Pad18)") (class "Default")
      (node (ref "MC2") (pin "18") (pinfunction "DNC_18") (pintype "passive"))
    )
    (net (code "67") (name "unconnected-(MC2-DNC-Pad19)") (class "Default")
      (node (ref "MC2") (pin "19") (pinfunction "DNC_19") (pintype "passive"))
    )
    (net (code "68") (name "unconnected-(MC2-PA0-Pad5)") (class "Default")
      (node (ref "MC2") (pin "5") (pinfunction "PA0_5") (pintype "power_in"))
    )
    (net (code "69") (name "unconnected-(MC2-PA3-Pad2)") (class "Default")
      (node (ref "MC2") (pin "2") (pinfunction "PA3_2") (pintype "power_in"))
    )
    (net (code "70") (name "unconnected-(MC2-PA7-Pad15)") (class "Default")
      (node (ref "MC2") (pin "15") (pinfunction "PA7_15") (pintype "power_in"))
    )
    (net (code "71") (name "unconnected-(MC2-PB1-Pad12)") (class "Default")
      (node (ref "MC2") (pin "12") (pinfunction "PB1_12") (pintype "power_in"))
    )
    (net (code "72") (name "unconnected-(R2-Pad3)") (class "Default")
      (node (ref "R2") (pin "3") (pinfunction "3_3") (pintype "passive"))
    )
    (net (code "73") (name "unconnected-(U1-DISCH-Pad7)") (class "Default")
      (node (ref "U1") (pin "7") (pinfunction "DISCH_7") (pintype "passive"))
    )
  )
)
